# Lumiboard_-_power_resistor_board.net
KiCad netlist of a schematic drawn in EAGLE
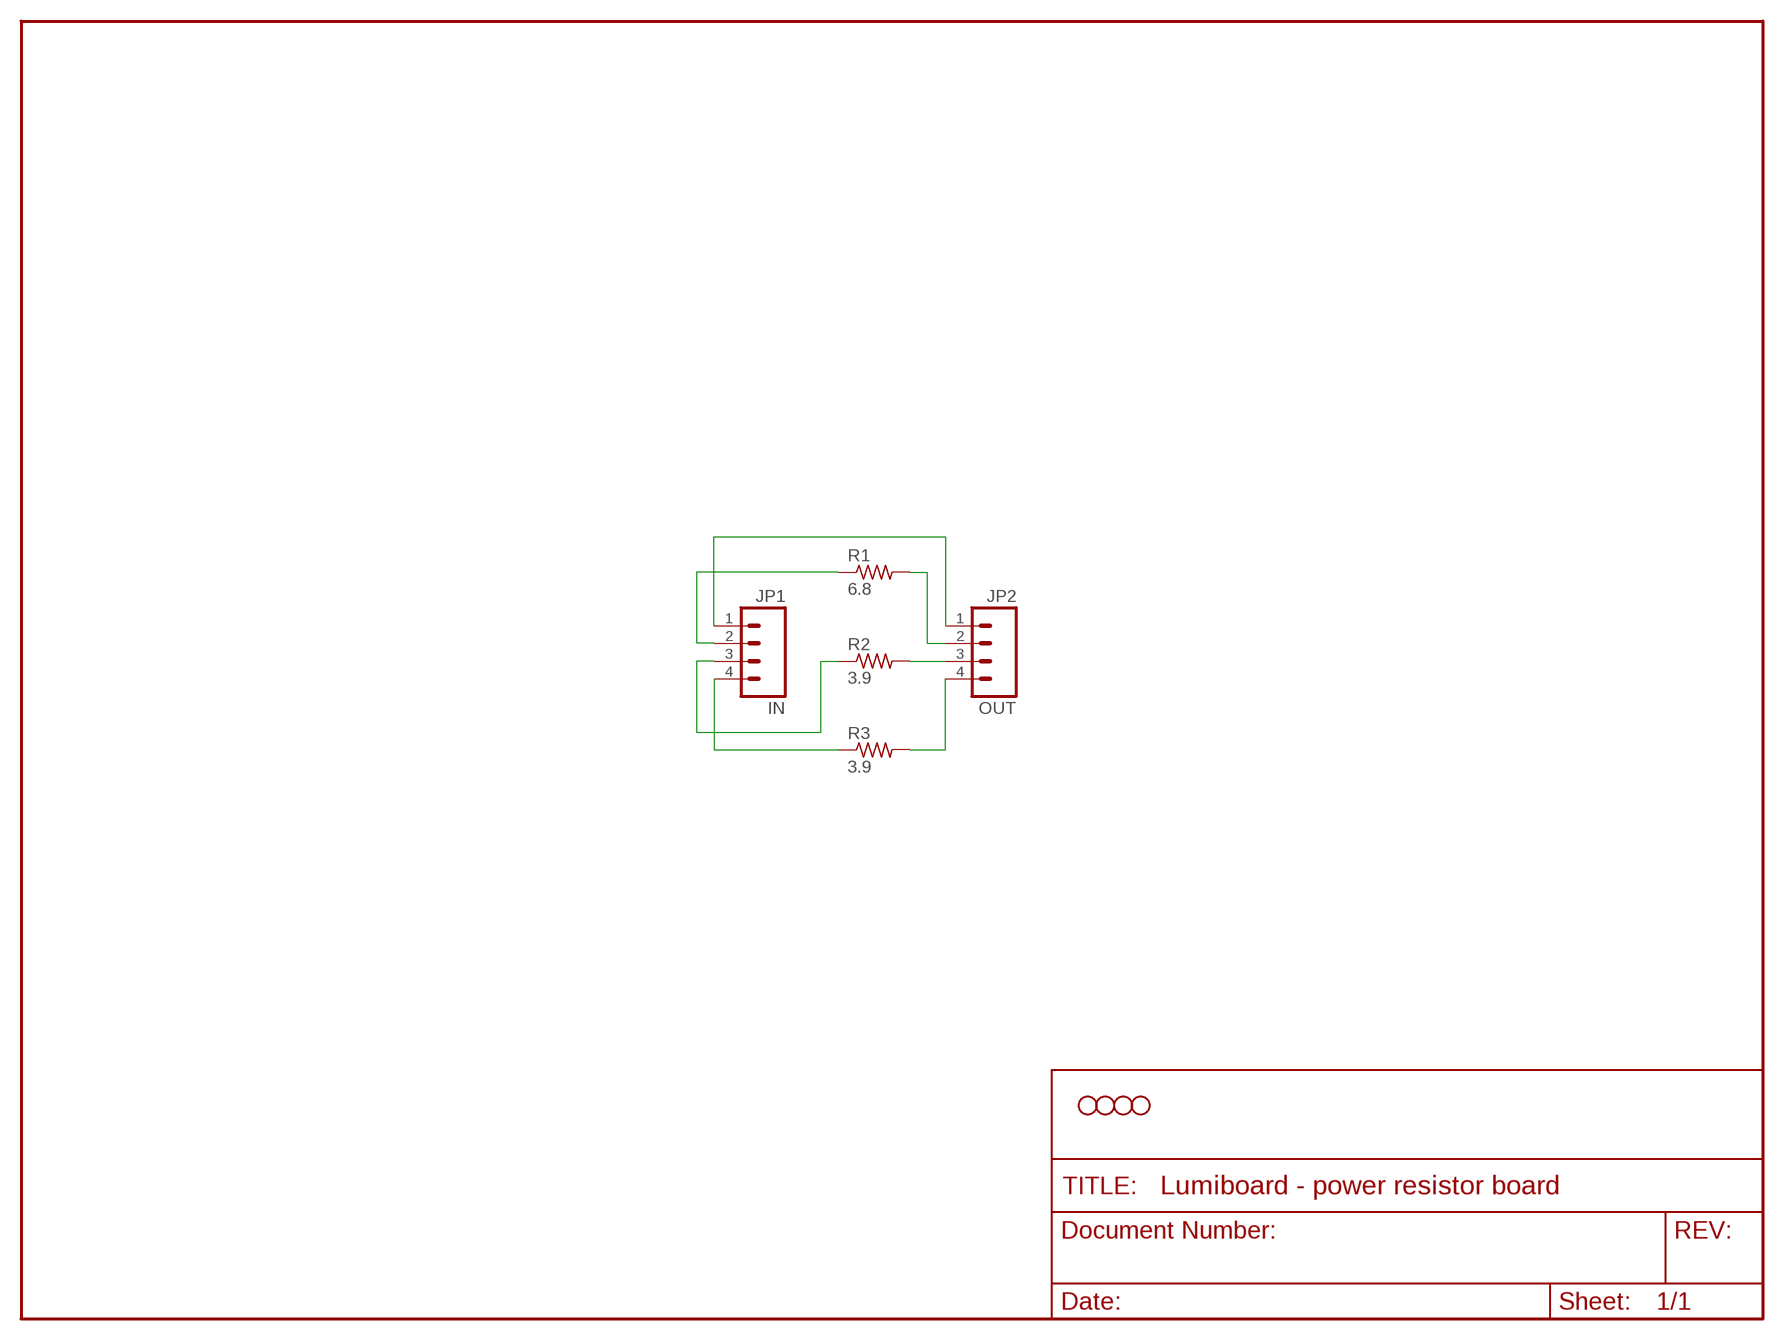
[diagram p0: schematic, sheet 1]

(export (version "E")
  (design (tool "Eeschema 10.0.6"))
  (components
    (comp (ref "IN")
      (value "JP1")
      (footprint "eagle-import:1X04")
      (libsource (lib "eagle-import") (part "M04PTH"))
    )
    (comp (ref "JP1")
      (value "STAND-OFF")
      (footprint "eagle-import:STAND-OFF")
      (libsource (lib "eagle-import") (part "STAND-OFF"))
    )
    (comp (ref "JP2")
      (value "STAND-OFF")
      (footprint "eagle-import:STAND-OFF")
      (libsource (lib "eagle-import") (part "STAND-OFF"))
    )
    (comp (ref "JP3")
      (value "STAND-OFF")
      (footprint "eagle-import:STAND-OFF")
      (libsource (lib "eagle-import") (part "STAND-OFF"))
    )
    (comp (ref "JP4")
      (value "STAND-OFF")
      (footprint "eagle-import:STAND-OFF")
      (libsource (lib "eagle-import") (part "STAND-OFF"))
    )
    (comp (ref "OUT")
      (value "JP2")
      (footprint "eagle-import:1X04")
      (libsource (lib "eagle-import") (part "M04PTH"))
    )
    (comp (ref "R1")
      (value "6.8")
      (footprint "eagle-import:0411_15")
      (libsource (lib "eagle-import") (part "R-US_0411/15"))
    )
    (comp (ref "R2")
      (value "3.9")
      (footprint "eagle-import:0411_15")
      (libsource (lib "eagle-import") (part "R-US_0411/15"))
    )
    (comp (ref "R3")
      (value "3.9")
      (footprint "eagle-import:0411_15")
      (libsource (lib "eagle-import") (part "R-US_0411/15"))
    )
  )
  (nets
    (net (code "1") (name "Net-(IN-Pad1)") (class "Default")
      (node (ref "IN") (pin "1") (pinfunction "1_1") (pintype "passive"))
      (node (ref "OUT") (pin "1") (pinfunction "1_1") (pintype "passive"))
    )
    (net (code "2") (name "Net-(IN-Pad2)") (class "Default")
      (node (ref "IN") (pin "2") (pinfunction "2_2") (pintype "passive"))
      (node (ref "R1") (pin "1") (pinfunction "1_1") (pintype "passive"))
    )
    (net (code "3") (name "Net-(IN-Pad3)") (class "Default")
      (node (ref "IN") (pin "3") (pinfunction "3_3") (pintype "passive"))
      (node (ref "R2") (pin "1") (pinfunction "1_1") (pintype "passive"))
    )
    (net (code "4") (name "Net-(IN-Pad4)") (class "Default")
      (node (ref "IN") (pin "4") (pinfunction "4_4") (pintype "passive"))
      (node (ref "R3") (pin "1") (pinfunction "1_1") (pintype "passive"))
    )
    (net (code "5") (name "Net-(OUT-Pad2)") (class "Default")
      (node (ref "OUT") (pin "2") (pinfunction "2_2") (pintype "passive"))
      (node (ref "R1") (pin "2") (pinfunction "2_2") (pintype "passive"))
    )
    (net (code "6") (name "Net-(OUT-Pad3)") (class "Default")
      (node (ref "OUT") (pin "3") (pinfunction "3_3") (pintype "passive"))
      (node (ref "R2") (pin "2") (pinfunction "2_2") (pintype "passive"))
    )
    (net (code "7") (name "Net-(OUT-Pad4)") (class "Default")
      (node (ref "OUT") (pin "4") (pinfunction "4_4") (pintype "passive"))
      (node (ref "R3") (pin "2") (pinfunction "2_2") (pintype "passive"))
    )
  )
)
